# Final.net
KiCad netlist of a schematic drawn in EAGLE
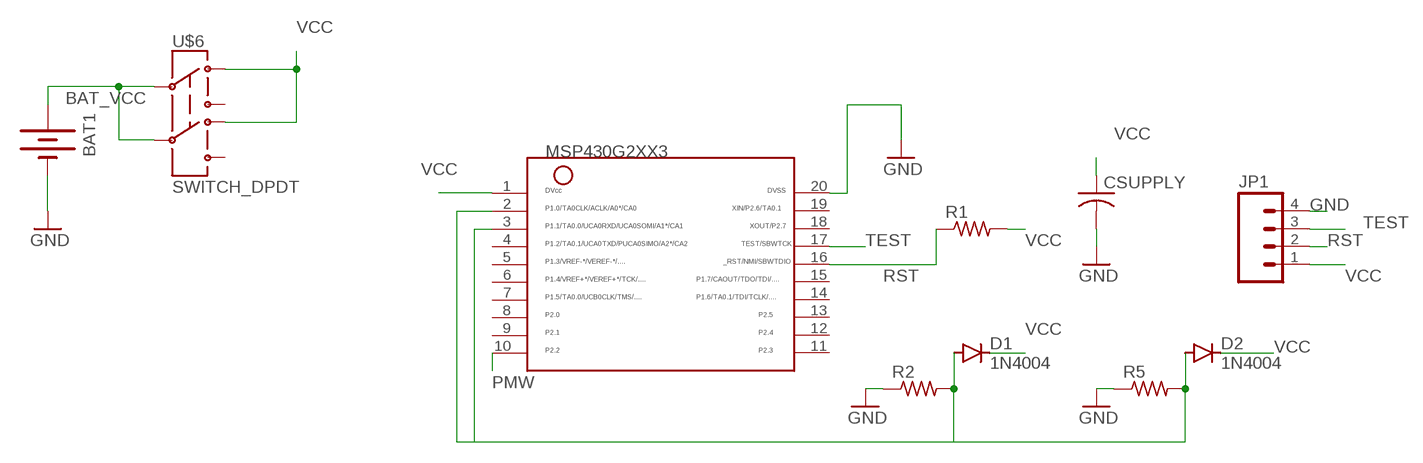
[diagram p0: schematic, sheet 1]

(export (version "E")
  (design (tool "Eeschema 10.0.6"))
  (components
    (comp (ref "BAT1")
      (value "BATTERY")
      (footprint "eagle-import:BATTERY_PACK_2AA")
      (libsource (lib "eagle-import") (part "BATTERY"))
    )
    (comp (ref "CSUPPLY")
      (value "C-USC1206")
      (footprint "eagle-import:C1206")
      (libsource (lib "eagle-import") (part "C-USC1206"))
    )
    (comp (ref "D1")
      (value "1N4004")
      (footprint "eagle-import:DO41-10")
      (libsource (lib "eagle-import") (part "1N4004"))
    )
    (comp (ref "D2")
      (value "1N4004")
      (footprint "eagle-import:DO41-10")
      (libsource (lib "eagle-import") (part "1N4004"))
    )
    (comp (ref "JP1")
      (value "M04LOCK")
      (footprint "eagle-import:1X04_LOCK")
      (libsource (lib "eagle-import") (part "M04LOCK"))
    )
    (comp (ref "R1")
      (value "R-US_R1206")
      (footprint "eagle-import:R1206")
      (libsource (lib "eagle-import") (part "R-US_R1206"))
    )
    (comp (ref "R2")
      (value "R-US_R1206")
      (footprint "eagle-import:R1206")
      (libsource (lib "eagle-import") (part "R-US_R1206"))
    )
    (comp (ref "R5")
      (value "R-US_R1206")
      (footprint "eagle-import:R1206")
      (libsource (lib "eagle-import") (part "R-US_R1206"))
    )
    (comp (ref "U$1")
      (value "MSP430G2XX3TSSOP")
      (footprint "eagle-import:PW20")
      (libsource (lib "eagle-import") (part "MSP430G2XX3TSSOP"))
    )
    (comp (ref "U$6")
      (value "SWITCH_DPDT")
      (footprint "eagle-import:JS_DPDT_TH")
      (libsource (lib "eagle-import") (part "SWITCH_DPDT"))
    )
  )
  (nets
    (net (code "1") (name "/BAT_VCC") (class "Default")
      (node (ref "BAT1") (pin "3V") (pinfunction "+_3V") (pintype "power_in"))
      (node (ref "U$6") (pin "2") (pinfunction "2_2") (pintype "bidirectional"))
      (node (ref "U$6") (pin "5") (pinfunction "5_5") (pintype "bidirectional"))
    )
    (net (code "2") (name "/PMW") (class "Default")
      (node (ref "U$1") (pin "10") (pinfunction "10_10") (pintype "bidirectional"))
    )
    (net (code "3") (name "/RST") (class "Default")
      (node (ref "JP1") (pin "2") (pinfunction "2_2") (pintype "passive"))
      (node (ref "R1") (pin "1") (pinfunction "1_1") (pintype "passive"))
      (node (ref "U$1") (pin "16") (pinfunction "16_16") (pintype "bidirectional"))
    )
    (net (code "4") (name "/TEST") (class "Default")
      (node (ref "JP1") (pin "3") (pinfunction "3_3") (pintype "passive"))
      (node (ref "U$1") (pin "17") (pinfunction "17_17") (pintype "bidirectional"))
    )
    (net (code "5") (name "/VCC") (class "Default")
      (node (ref "CSUPPLY") (pin "1") (pinfunction "1_1") (pintype "passive"))
      (node (ref "D1") (pin "C") (pinfunction "C_C") (pintype "passive"))
      (node (ref "D2") (pin "C") (pinfunction "C_C") (pintype "passive"))
      (node (ref "JP1") (pin "1") (pinfunction "1_1") (pintype "passive"))
      (node (ref "R1") (pin "2") (pinfunction "2_2") (pintype "passive"))
      (node (ref "U$1") (pin "1") (pinfunction "1_1") (pintype "bidirectional"))
      (node (ref "U$6") (pin "1") (pinfunction "1_1") (pintype "bidirectional"))
      (node (ref "U$6") (pin "4") (pinfunction "4_4") (pintype "bidirectional"))
    )
    (net (code "6") (name "GND") (class "Default")
      (node (ref "BAT1") (pin "GND") (pinfunction "-_GND") (pintype "power_in"))
      (node (ref "CSUPPLY") (pin "2") (pinfunction "2_2") (pintype "passive"))
      (node (ref "JP1") (pin "4") (pinfunction "4_4") (pintype "passive"))
      (node (ref "R2") (pin "1") (pinfunction "1_1") (pintype "passive"))
      (node (ref "R5") (pin "1") (pinfunction "1_1") (pintype "passive"))
      (node (ref "U$1") (pin "20") (pinfunction "20_20") (pintype "bidirectional"))
    )
    (net (code "7") (name "Net-(D1-PadA)") (class "Default")
      (node (ref "D1") (pin "A") (pinfunction "A_A") (pintype "passive"))
      (node (ref "R2") (pin "2") (pinfunction "2_2") (pintype "passive"))
      (node (ref "U$1") (pin "2") (pinfunction "2_2") (pintype "bidirectional"))
    )
    (net (code "8") (name "Net-(D2-PadA)") (class "Default")
      (node (ref "D2") (pin "A") (pinfunction "A_A") (pintype "passive"))
      (node (ref "R5") (pin "2") (pinfunction "2_2") (pintype "passive"))
      (node (ref "U$1") (pin "3") (pinfunction "3_3") (pintype "bidirectional"))
    )
    (net (code "9") (name "unconnected-(U$1-Pad4)") (class "Default")
      (node (ref "U$1") (pin "4") (pinfunction "4_4") (pintype "bidirectional"))
    )
    (net (code "10") (name "unconnected-(U$1-Pad5)") (class "Default")
      (node (ref "U$1") (pin "5") (pinfunction "5_5") (pintype "bidirectional"))
    )
    (net (code "11") (name "unconnected-(U$1-Pad6)") (class "Default")
      (node (ref "U$1") (pin "6") (pinfunction "6_6") (pintype "bidirectional"))
    )
    (net (code "12") (name "unconnected-(U$1-Pad7)") (class "Default")
      (node (ref "U$1") (pin "7") (pinfunction "7_7") (pintype "bidirectional"))
    )
    (net (code "13") (name "unconnected-(U$1-Pad8)") (class "Default")
      (node (ref "U$1") (pin "8") (pinfunction "8_8") (pintype "bidirectional"))
    )
    (net (code "14") (name "unconnected-(U$1-Pad9)") (class "Default")
      (node (ref "U$1") (pin "9") (pinfunction "9_9") (pintype "bidirectional"))
    )
    (net (code "15") (name "unconnected-(U$1-Pad11)") (class "Default")
      (node (ref "U$1") (pin "11") (pinfunction "11_11") (pintype "bidirectional"))
    )
    (net (code "16") (name "unconnected-(U$1-Pad12)") (class "Default")
      (node (ref "U$1") (pin "12") (pinfunction "12_12") (pintype "bidirectional"))
    )
    (net (code "17") (name "unconnected-(U$1-Pad13)") (class "Default")
      (node (ref "U$1") (pin "13") (pinfunction "13_13") (pintype "bidirectional"))
    )
    (net (code "18") (name "unconnected-(U$1-Pad14)") (class "Default")
      (node (ref "U$1") (pin "14") (pinfunction "14_14") (pintype "bidirectional"))
    )
    (net (code "19") (name "unconnected-(U$1-Pad15)") (class "Default")
      (node (ref "U$1") (pin "15") (pinfunction "15_15") (pintype "bidirectional"))
    )
    (net (code "20") (name "unconnected-(U$1-Pad18)") (class "Default")
      (node (ref "U$1") (pin "18") (pinfunction "18_18") (pintype "bidirectional"))
    )
    (net (code "21") (name "unconnected-(U$1-Pad19)") (class "Default")
      (node (ref "U$1") (pin "19") (pinfunction "19_19") (pintype "bidirectional"))
    )
    (net (code "22") (name "unconnected-(U$6-Pad3)") (class "Default")
      (node (ref "U$6") (pin "3") (pinfunction "3_3") (pintype "bidirectional"))
    )
    (net (code "23") (name "unconnected-(U$6-Pad6)") (class "Default")
      (node (ref "U$6") (pin "6") (pinfunction "6_6") (pintype "bidirectional"))
    )
  )
)
